# FM-Superregenerative-Receiver-1.net
KiCad netlist of a schematic drawn in EAGLE
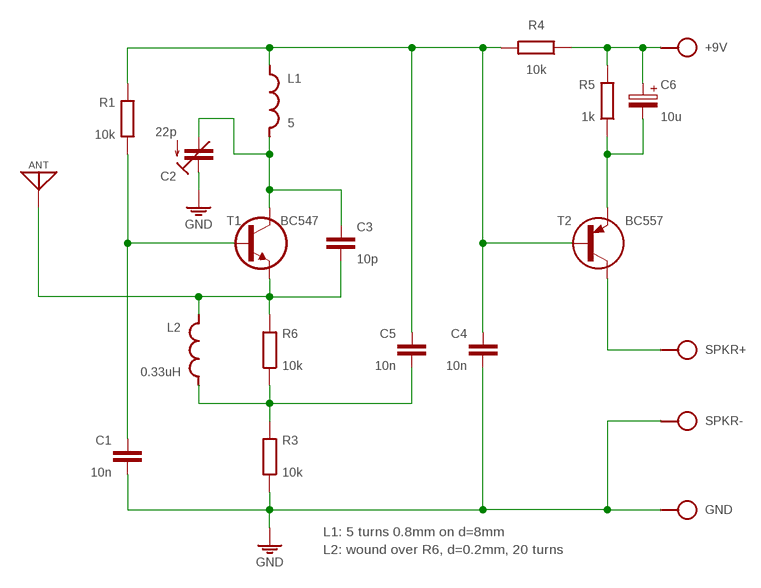
[diagram p0: schematic, sheet 1]

(export (version "E")
  (design (tool "Eeschema 10.0.6"))
  (components
    (comp (ref "+9V")
      (value "SPAD")
      (footprint "eagle-import:SPAD")
      (libsource (lib "eagle-import") (part "SPAD"))
    )
    (comp (ref "ANT")
      (value "ANT")
      (footprint "eagle-import:SPAD")
      (libsource (lib "eagle-import") (part "ANT"))
    )
    (comp (ref "C1")
      (value "10n")
      (footprint "eagle-import:C050-025X075")
      (libsource (lib "eagle-import") (part "C050-025X075"))
    )
    (comp (ref "C2")
      (value "22p")
      (footprint "eagle-import:TRIM-2222-808")
      (libsource (lib "eagle-import") (part "C-TR-PH201272222-808-2PIN"))
    )
    (comp (ref "C3")
      (value "10p")
      (footprint "eagle-import:C050-020X036")
      (libsource (lib "eagle-import") (part "C050-020X036"))
    )
    (comp (ref "C4")
      (value "10n")
      (footprint "eagle-import:C050-025X075")
      (libsource (lib "eagle-import") (part "C050-025X075"))
    )
    (comp (ref "C5")
      (value "10n")
      (footprint "eagle-import:C050-025X075")
      (libsource (lib "eagle-import") (part "C050-025X075"))
    )
    (comp (ref "C6")
      (value "10u")
      (footprint "eagle-import:E2,5-3")
      (libsource (lib "eagle-import") (part "CPOLE2,5-3"))
    )
    (comp (ref "GND")
      (value "SPAD")
      (footprint "eagle-import:SPAD")
      (libsource (lib "eagle-import") (part "SPAD"))
    )
    (comp (ref "L1")
      (value "5")
      (footprint "eagle-import:L-02_7V")
      (libsource (lib "eagle-import") (part "L-SHORT02/7V"))
    )
    (comp (ref "L2")
      (value "0.33uH")
      (footprint "eagle-import:L-02_7V")
      (libsource (lib "eagle-import") (part "L-SHORT02/7V"))
    )
    (comp (ref "R1")
      (value "10k")
      (footprint "eagle-import:0202_7")
      (libsource (lib "eagle-import") (part "R0202/7"))
    )
    (comp (ref "R3")
      (value "10k")
      (footprint "eagle-import:0202_7-V")
      (libsource (lib "eagle-import") (part "R0202/7-V"))
    )
    (comp (ref "R4")
      (value "10k")
      (footprint "eagle-import:0202_7")
      (libsource (lib "eagle-import") (part "R0202/7"))
    )
    (comp (ref "R5")
      (value "1k")
      (footprint "eagle-import:0202_7-V")
      (libsource (lib "eagle-import") (part "R0202/7-V"))
    )
    (comp (ref "R6")
      (value "10k")
      (footprint "eagle-import:0202_7-V")
      (libsource (lib "eagle-import") (part "R0202/7-V"))
    )
    (comp (ref "SPKR+")
      (value "SPAD")
      (footprint "eagle-import:SPAD")
      (libsource (lib "eagle-import") (part "SPAD"))
    )
    (comp (ref "SPKR-")
      (value "SPAD")
      (footprint "eagle-import:SPAD")
      (libsource (lib "eagle-import") (part "SPAD"))
    )
    (comp (ref "T1")
      (value "BC547")
      (footprint "eagle-import:TO92-CBE")
      (libsource (lib "eagle-import") (part "BC547CBE"))
    )
    (comp (ref "T2")
      (value "BC557")
      (footprint "eagle-import:TO92-CBE")
      (libsource (lib "eagle-import") (part "BC557CBE"))
    )
  )
  (nets
    (net (code "1") (name "GND") (class "Default")
      (node (ref "C1") (pin "2") (pinfunction "2_2") (pintype "passive"))
      (node (ref "C2") (pin "1") (pinfunction "E_1") (pintype "passive"))
      (node (ref "C4") (pin "2") (pinfunction "2_2") (pintype "passive"))
      (node (ref "GND") (pin "1") (pinfunction "P$1_1") (pintype "bidirectional"))
      (node (ref "R3") (pin "1") (pinfunction "1_1") (pintype "passive"))
      (node (ref "SPKR-") (pin "1") (pinfunction "P$1_1") (pintype "bidirectional"))
    )
    (net (code "2") (name "Net-(+9V-P$1)") (class "Default")
      (node (ref "+9V") (pin "1") (pinfunction "P$1_1") (pintype "bidirectional"))
      (node (ref "C6") (pin "+") (pinfunction "+_+") (pintype "passive"))
      (node (ref "R4") (pin "1") (pinfunction "1_1") (pintype "passive"))
      (node (ref "R5") (pin "2") (pinfunction "2_2") (pintype "passive"))
    )
    (net (code "3") (name "Net-(ANT-Pad1)") (class "Default")
      (node (ref "ANT") (pin "1") (pinfunction "1_1") (pintype "output"))
      (node (ref "C3") (pin "2") (pinfunction "2_2") (pintype "passive"))
      (node (ref "L2") (pin "1") (pinfunction "1_1") (pintype "passive"))
      (node (ref "R6") (pin "2") (pinfunction "2_2") (pintype "passive"))
      (node (ref "T1") (pin "E") (pinfunction "E_E") (pintype "passive"))
    )
    (net (code "4") (name "Net-(C1-Pad1)") (class "Default")
      (node (ref "C1") (pin "1") (pinfunction "1_1") (pintype "passive"))
      (node (ref "R1") (pin "1") (pinfunction "1_1") (pintype "passive"))
      (node (ref "T1") (pin "B") (pinfunction "B_B") (pintype "passive"))
    )
    (net (code "5") (name "Net-(C2-A)") (class "Default")
      (node (ref "C2") (pin "2") (pinfunction "A_2") (pintype "passive"))
      (node (ref "C3") (pin "1") (pinfunction "1_1") (pintype "passive"))
      (node (ref "L1") (pin "2") (pinfunction "2_2") (pintype "passive"))
      (node (ref "T1") (pin "C") (pinfunction "C_C") (pintype "passive"))
    )
    (net (code "6") (name "Net-(C4-Pad1)") (class "Default")
      (node (ref "C4") (pin "1") (pinfunction "1_1") (pintype "passive"))
      (node (ref "C5") (pin "1") (pinfunction "1_1") (pintype "passive"))
      (node (ref "L1") (pin "1") (pinfunction "1_1") (pintype "passive"))
      (node (ref "R1") (pin "2") (pinfunction "2_2") (pintype "passive"))
      (node (ref "R4") (pin "2") (pinfunction "2_2") (pintype "passive"))
      (node (ref "T2") (pin "B") (pinfunction "B_B") (pintype "passive"))
    )
    (net (code "7") (name "Net-(C5-Pad2)") (class "Default")
      (node (ref "C5") (pin "2") (pinfunction "2_2") (pintype "passive"))
      (node (ref "L2") (pin "2") (pinfunction "2_2") (pintype "passive"))
      (node (ref "R3") (pin "2") (pinfunction "2_2") (pintype "passive"))
      (node (ref "R6") (pin "1") (pinfunction "1_1") (pintype "passive"))
    )
    (net (code "8") (name "Net-(C6-Pad-)") (class "Default")
      (node (ref "C6") (pin "-") (pinfunction "-_-") (pintype "passive"))
      (node (ref "R5") (pin "1") (pinfunction "1_1") (pintype "passive"))
      (node (ref "T2") (pin "E") (pinfunction "E_E") (pintype "passive"))
    )
    (net (code "9") (name "Net-(SPKR+-P$1)") (class "Default")
      (node (ref "SPKR+") (pin "1") (pinfunction "P$1_1") (pintype "bidirectional"))
      (node (ref "T2") (pin "C") (pinfunction "C_C") (pintype "passive"))
    )
  )
)
